# High-Side_Driver.net
KiCad netlist of a schematic drawn in Altium Designer
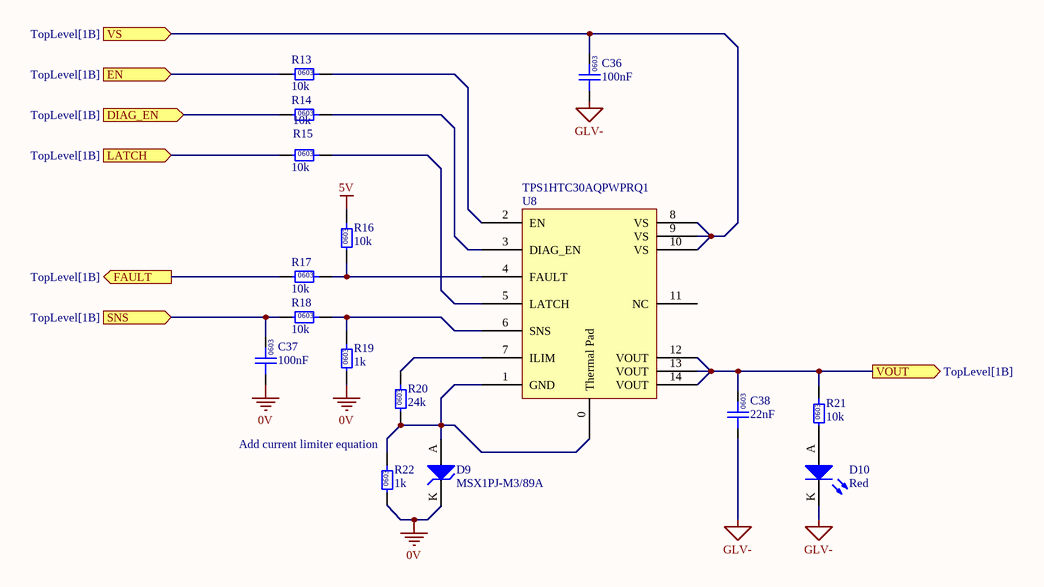
[diagram p0: High-Side Driver.SchDoc]

(export (version "E")
  (design (tool "Eeschema 10.0.6"))
  (components
    (comp (ref "C36")
      (value "100nF")
      (footprint "0603")
      (fields
        (field (name "PART NUMBER") "GCM188L81H104KA57D")
        (field (name "MANUFACTURER") "muRata")
        (field (name "TOLERANCE") "±10%")
      )
      (libsource (lib "ts_standard_library") (part "Capacitor 0603"))
    )
    (comp (ref "C37")
      (value "100nF")
      (footprint "0603")
      (fields
        (field (name "PART NUMBER") "GCM188L81H104KA57D")
        (field (name "MANUFACTURER") "muRata")
        (field (name "TOLERANCE") "±10%")
      )
      (libsource (lib "ts_standard_library") (part "Capacitor 0603"))
    )
    (comp (ref "C38")
      (value "22nF")
      (footprint "0603")
      (fields
        (field (name "PART NUMBER") "GCM188R71H223KA37J")
        (field (name "MANUFACTURER") "Murata Electronics")
        (field (name "TOLERANCE") "±10%")
      )
      (libsource (lib "ts_standard_library") (part "Capacitor 0603"))
    )
    (comp (ref "D9")
      (value "MSX1PJ-M3/89A")
      (footprint "VISHAY DO-219")
      (fields (field (name "MANUFACTURER") "Vishay General Semiconductor - Diodes Division"))
      (libsource (lib "ts_standard_library") (part "Zener Diode"))
    )
    (comp (ref "D10")
      (value "Red")
      (footprint "0805 LED")
      (description "Red LED Indication - Discrete 1.75V 0805 (2012 Metric)")
      (fields (field (name "PART NUMBER") "SML-210LTT86") (field (name "MANUFACTURER") "ROHM Semiconductor"))
      (libsource (lib "ts_standard_library") (part "LED"))
    )
    (comp (ref "R13")
      (value "10k")
      (footprint "0603")
      (fields
        (field (name "PART NUMBER") "RC0603FR-0710KL")
        (field (name "MANUFACTURER") "YAGEO")
        (field (name "TOLERANCE") "0.01")
      )
      (libsource (lib "ts_standard_library") (part "Resistor 0603"))
    )
    (comp (ref "R14")
      (value "10k")
      (footprint "0603")
      (fields
        (field (name "PART NUMBER") "RC0603FR-0710KL")
        (field (name "MANUFACTURER") "YAGEO")
        (field (name "TOLERANCE") "0.01")
      )
      (libsource (lib "ts_standard_library") (part "Resistor 0603"))
    )
    (comp (ref "R15")
      (value "10k")
      (footprint "0603")
      (fields
        (field (name "PART NUMBER") "RC0603FR-0710KL")
        (field (name "MANUFACTURER") "YAGEO")
        (field (name "TOLERANCE") "0.01")
      )
      (libsource (lib "ts_standard_library") (part "Resistor 0603"))
    )
    (comp (ref "R16")
      (value "10k")
      (footprint "0603")
      (fields
        (field (name "PART NUMBER") "RC0603FR-0710KL")
        (field (name "MANUFACTURER") "YAGEO")
        (field (name "TOLERANCE") "0.01")
      )
      (libsource (lib "ts_standard_library") (part "Resistor 0603"))
    )
    (comp (ref "R17")
      (value "10k")
      (footprint "0603")
      (fields
        (field (name "PART NUMBER") "RC0603FR-0710KL")
        (field (name "MANUFACTURER") "YAGEO")
        (field (name "TOLERANCE") "0.01")
      )
      (libsource (lib "ts_standard_library") (part "Resistor 0603"))
    )
    (comp (ref "R18")
      (value "10k")
      (footprint "0603")
      (fields
        (field (name "PART NUMBER") "RC0603FR-0710KL")
        (field (name "MANUFACTURER") "YAGEO")
        (field (name "TOLERANCE") "0.01")
      )
      (libsource (lib "ts_standard_library") (part "Resistor 0603"))
    )
    (comp (ref "R19")
      (value "1k")
      (footprint "0603")
      (fields
        (field (name "PART NUMBER") "RC0603FR-071KL")
        (field (name "MANUFACTURER") "YAGEO")
        (field (name "TOLERANCE") "0.01")
      )
      (libsource (lib "ts_standard_library") (part "Resistor 0603"))
    )
    (comp (ref "R20")
      (value "24k")
      (footprint "0603")
      (fields
        (field (name "PART NUMBER") "RC0603FR-7W24KL")
        (field (name "MANUFACTURER") "YAGEO")
        (field (name "TOLERANCE") "0.01")
      )
      (libsource (lib "ts_standard_library") (part "Resistor 0603"))
    )
    (comp (ref "R21")
      (value "10k")
      (footprint "0603")
      (fields
        (field (name "PART NUMBER") "RC0603FR-0710KL")
        (field (name "MANUFACTURER") "YAGEO")
        (field (name "TOLERANCE") "0.01")
      )
      (libsource (lib "ts_standard_library") (part "Resistor 0603"))
    )
    (comp (ref "R22")
      (value "1k")
      (footprint "0603")
      (fields
        (field (name "PART NUMBER") "RC0603FR-071KL")
        (field (name "MANUFACTURER") "YAGEO")
        (field (name "TOLERANCE") "0.01")
      )
      (libsource (lib "ts_standard_library") (part "Resistor 0603"))
    )
    (comp (ref "U8")
      (value "TPS1HTC30AQPWPRQ1")
      (footprint "TI_14_TSSOP")
      (description "AUTOMOTIVE, 60-V, 6-A, 30-M, ONE")
      (libsource (lib "ts_standard_library") (part "TPS1HTC30AQPWPRQ1"))
    )
  )
  (nets
    (net (code "1") (name "/DIAG_EN") (class "Default")
      (node (ref "R14") (pin "1") (pinfunction "1_1") (pintype "passive"))
    )
    (net (code "2") (name "/EN") (class "Default")
      (node (ref "R13") (pin "1") (pinfunction "1_1") (pintype "passive"))
    )
    (net (code "3") (name "/FAULT") (class "Default")
      (node (ref "R17") (pin "1") (pinfunction "1_1") (pintype "passive"))
    )
    (net (code "4") (name "/LATCH") (class "Default")
      (node (ref "R15") (pin "1") (pinfunction "1_1") (pintype "passive"))
    )
    (net (code "5") (name "/SNS") (class "Default")
      (node (ref "C37") (pin "2") (pinfunction "2_2") (pintype "passive"))
      (node (ref "R18") (pin "1") (pinfunction "1_1") (pintype "passive"))
    )
    (net (code "6") (name "/VOUT") (class "Default")
      (node (ref "C38") (pin "2") (pinfunction "2_2") (pintype "passive"))
      (node (ref "R21") (pin "2") (pinfunction "2_2") (pintype "passive"))
      (node (ref "U8") (pin "12") (pinfunction "VOUT_12") (pintype "passive"))
      (node (ref "U8") (pin "13") (pinfunction "VOUT_13") (pintype "passive"))
      (node (ref "U8") (pin "14") (pinfunction "VOUT_14") (pintype "passive"))
    )
    (net (code "7") (name "/VS") (class "Default")
      (node (ref "C36") (pin "2") (pinfunction "2_2") (pintype "passive"))
      (node (ref "U8") (pin "10") (pinfunction "VS_10") (pintype "passive"))
      (node (ref "U8") (pin "8") (pinfunction "VS_8") (pintype "passive"))
      (node (ref "U8") (pin "9") (pinfunction "VS_9") (pintype "passive"))
    )
    (net (code "8") (name "0V") (class "Default")
      (node (ref "C37") (pin "1") (pinfunction "1_1") (pintype "passive"))
      (node (ref "D9") (pin "K") (pinfunction "K_K") (pintype "passive"))
      (node (ref "R19") (pin "1") (pinfunction "1_1") (pintype "passive"))
      (node (ref "R22") (pin "1") (pinfunction "1_1") (pintype "passive"))
    )
    (net (code "9") (name "5V") (class "Default")
      (node (ref "R16") (pin "2") (pinfunction "2_2") (pintype "passive"))
    )
    (net (code "10") (name "GLV-") (class "Default")
      (node (ref "C36") (pin "1") (pinfunction "1_1") (pintype "passive"))
      (node (ref "C38") (pin "1") (pinfunction "1_1") (pintype "passive"))
      (node (ref "D10") (pin "K") (pinfunction "K_K") (pintype "passive"))
    )
    (net (code "11") (name "Net-(D10-PadA)") (class "Default")
      (node (ref "D10") (pin "A") (pinfunction "A_A") (pintype "passive"))
      (node (ref "R21") (pin "1") (pinfunction "1_1") (pintype "passive"))
    )
    (net (code "12") (name "Net-(U8-DIAG_EN)") (class "Default")
      (node (ref "R14") (pin "2") (pinfunction "2_2") (pintype "passive"))
      (node (ref "U8") (pin "3") (pinfunction "DIAG_EN_3") (pintype "passive"))
    )
    (net (code "13") (name "Net-(U8-EN)") (class "Default")
      (node (ref "R13") (pin "2") (pinfunction "2_2") (pintype "passive"))
      (node (ref "U8") (pin "2") (pinfunction "EN_2") (pintype "passive"))
    )
    (net (code "14") (name "Net-(U8-FAULT)") (class "Default")
      (node (ref "R16") (pin "1") (pinfunction "1_1") (pintype "passive"))
      (node (ref "R17") (pin "2") (pinfunction "2_2") (pintype "passive"))
      (node (ref "U8") (pin "4") (pinfunction "FAULT_4") (pintype "passive"))
    )
    (net (code "15") (name "Net-(U8-GND)") (class "Default")
      (node (ref "D9") (pin "A") (pinfunction "A_A") (pintype "passive"))
      (node (ref "R20") (pin "1") (pinfunction "1_1") (pintype "passive"))
      (node (ref "R22") (pin "2") (pinfunction "2_2") (pintype "passive"))
      (node (ref "U8") (pin "0") (pinfunction "Thermal_Pad_0") (pintype "passive"))
      (node (ref "U8") (pin "1") (pinfunction "GND_1") (pintype "passive"))
    )
    (net (code "16") (name "Net-(U8-ILIM)") (class "Default")
      (node (ref "R20") (pin "2") (pinfunction "2_2") (pintype "passive"))
      (node (ref "U8") (pin "7") (pinfunction "ILIM_7") (pintype "passive"))
    )
    (net (code "17") (name "Net-(U8-LATCH)") (class "Default")
      (node (ref "R15") (pin "2") (pinfunction "2_2") (pintype "passive"))
      (node (ref "U8") (pin "5") (pinfunction "LATCH_5") (pintype "passive"))
    )
    (net (code "18") (name "Net-(U8-SNS)") (class "Default")
      (node (ref "R18") (pin "2") (pinfunction "2_2") (pintype "passive"))
      (node (ref "R19") (pin "2") (pinfunction "2_2") (pintype "passive"))
      (node (ref "U8") (pin "6") (pinfunction "SNS_6") (pintype "passive"))
    )
    (net (code "19") (name "unconnected-(U8-NC-Pad11)") (class "Default")
      (node (ref "U8") (pin "11") (pinfunction "NC_11") (pintype "passive"))
    )
  )
)
